# 1_2.net
KiCad netlist of a schematic drawn in Altium Designer
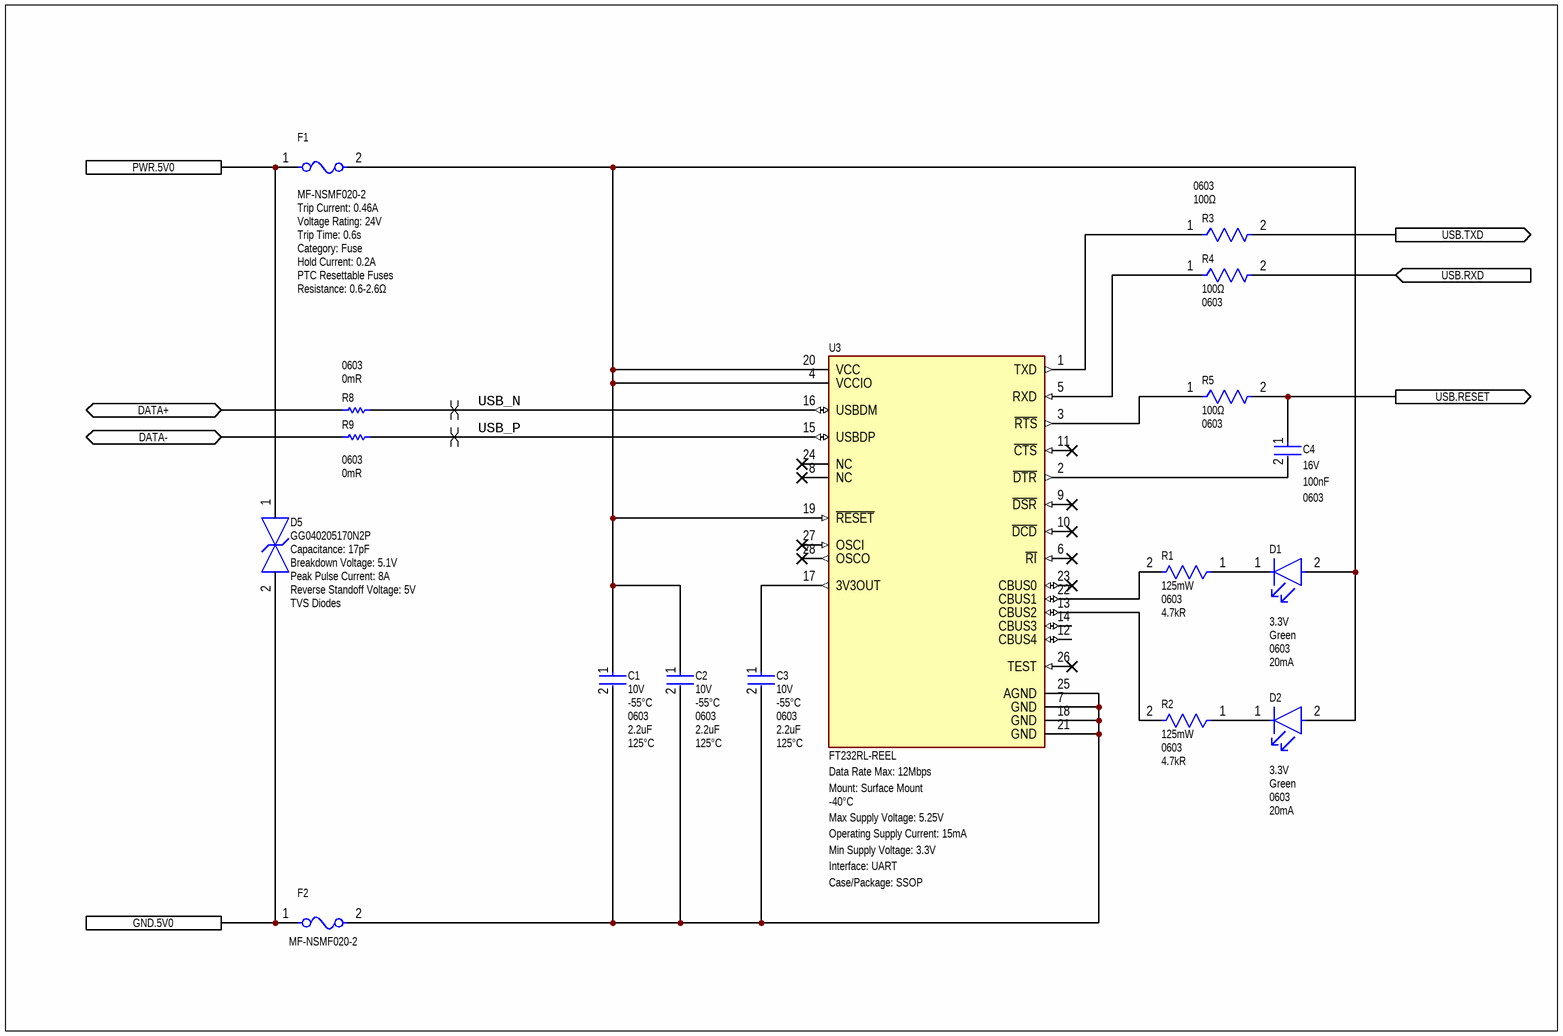
[diagram p0: Блок1.2.SchDoc]

(export (version "E")
  (design (tool "Eeschema 10.0.6"))
  (components
    (comp (ref "C1")
      (value "CL10B225KP8NFNC")
      (footprint "FP-CL10-IPC_A")
      (description "Cap Ceramic 2.2uF 10V X7R ±10% Pad SMD 0603 +125°C T/R")
      (fields
        (field (name "VOLTAGE RATING") "10V")
        (field (name "MIN OPERATING TEMPERATURE") "-55°C")
        (field (name "CASE CODE (IMPERIAL)") "0603")
        (field (name "CAPACITANCE") "2.2uF")
        (field (name "MAX OPERATING TEMPERATURE") "125°C")
        (field (name "TOLERANCE") "10%")
      )
      (libsource (lib "Altium Content Vault") (part "b4654b650e69147ec39a6b967a45e02"))
    )
    (comp (ref "C2")
      (value "CL10B225KP8NFNC")
      (footprint "FP-CL10-IPC_A")
      (description "Cap Ceramic 2.2uF 10V X7R ±10% Pad SMD 0603 +125°C T/R")
      (fields
        (field (name "VOLTAGE RATING") "10V")
        (field (name "MIN OPERATING TEMPERATURE") "-55°C")
        (field (name "CASE CODE (IMPERIAL)") "0603")
        (field (name "CAPACITANCE") "2.2uF")
        (field (name "MAX OPERATING TEMPERATURE") "125°C")
        (field (name "TOLERANCE") "10%")
      )
      (libsource (lib "Altium Content Vault") (part "b4654b650e69147ec39a6b967a45e02"))
    )
    (comp (ref "C3")
      (value "CL10B225KP8NFNC")
      (footprint "FP-CL10-IPC_A")
      (description "Cap Ceramic 2.2uF 10V X7R ±10% Pad SMD 0603 +125°C T/R")
      (fields
        (field (name "VOLTAGE RATING") "10V")
        (field (name "MIN OPERATING TEMPERATURE") "-55°C")
        (field (name "CASE CODE (IMPERIAL)") "0603")
        (field (name "CAPACITANCE") "2.2uF")
        (field (name "MAX OPERATING TEMPERATURE") "125°C")
        (field (name "TOLERANCE") "10%")
      )
      (libsource (lib "Altium Content Vault") (part "b4654b650e69147ec39a6b967a45e02"))
    )
    (comp (ref "C4")
      (value "CL10B104JO8NNND")
      (footprint "FP-CL10-IPC_B")
      (description "Cap Ceramic 100nF 16V X7R ±5% Pad SMD 0603 +125°C T/R")
      (fields
        (field (name "VOLTAGE RATING (DC)") "16V")
        (field (name "TOLERANCE") "5%")
        (field (name "CAPACITANCE") "100nF")
        (field (name "CASE/PACKAGE") "0603")
      )
      (libsource (lib "Altium Content Vault") (part "b4654b650e69147ec39a6b967a45e02"))
    )
    (comp (ref "D1")
      (value "APT1608ZGCK")
      (footprint "FP-APT1608ZGCK-MFG")
      (description "LED GREEN CLEAR CHIP SMD")
      (fields
        (field (name "FORWARD VOLTAGE") "3.3V")
        (field (name "COLOR") "Green")
        (field (name "CASE/PACKAGE") "0603")
        (field (name "FORWARD CURRENT") "20mA")
      )
      (libsource (lib "Altium Content Vault") (part "8706943c75ba83719d021d2fdc84c58"))
    )
    (comp (ref "D2")
      (value "APT1608ZGCK")
      (footprint "FP-APT1608ZGCK-MFG")
      (description "LED GREEN CLEAR CHIP SMD")
      (fields
        (field (name "FORWARD VOLTAGE") "3.3V")
        (field (name "COLOR") "Green")
        (field (name "CASE/PACKAGE") "0603")
        (field (name "FORWARD CURRENT") "20mA")
      )
      (libsource (lib "Altium Content Vault") (part "8706943c75ba83719d021d2fdc84c58"))
    )
    (comp (ref "D5")
      (value "GG040205170N2P")
      (footprint "FP-GG0402-IPC_A")
      (description "TVS DIODE 5V 10V 0402")
      (fields
        (field (name "OCTOPART") "https://octopart.com/gg040205170n2p-avx-81066082")
        (field (name "CAPACITANCE") "17pF")
        (field (name "MANUFACTURER") "AVX")
        (field (name "BREAKDOWN VOLTAGE") "5.1V")
        (field (name "PEAK PULSE CURRENT") "8A")
        (field (name "REVERSE STANDOFF VOLTAGE") "5V")
        (field (name "DEVICE CLASS L2") "TVS Diodes")
      )
      (libsource (lib "Altium Content Vault") (part "11bd9d59d340f0612179daf16ad9b72"))
    )
    (comp (ref "F1")
      (value "MF-NSMF020-2")
      (footprint "FP-MF-NSMF020-2-MFG")
      (description "PTC RESET FUSE 24V 200MA 1206")
      (fields
        (field (name "TRIP CURRENT") "0.46A")
        (field (name "VOLTAGE RATING") "24V")
        (field (name "TRIP TIME") "0.6s")
        (field (name "CATEGORY") "Fuse")
        (field (name "HOLD CURRENT") "0.2A")
        (field (name "DEVICE CLASS L2") "PTC Resettable Fuses")
        (field (name "MANUFACTURER") "Bourns")
        (field (name "OCTOPART") "https://octopart.com/mf-nsmf020-2-bourns-94649")
        (field (name "RESISTANCE") "0.6-2.6Ω")
      )
      (libsource (lib "Altium Content Vault") (part "5bcf9b9f640e542cf0359d10258e979"))
    )
    (comp (ref "F2")
      (value "MF-NSMF020-2")
      (footprint "FP-MF-NSMF020-2-MFG")
      (description "PTC RESET FUSE 24V 200MA 1206")
      (fields
        (field (name "MANUFACTURER") "Bourns")
        (field (name "OCTOPART") "https://octopart.com/mf-nsmf020-2-bourns-94649")
      )
      (libsource (lib "Altium Content Vault") (part "5bcf9b9f640e542cf0359d10258e979"))
    )
    (comp (ref "R1")
      (value "MCT06030C4701FP500")
      (footprint "FP-MCT0603-MFG")
      (description "RES SMD 100 OHM 1% 1/8W 0603")
      (fields
        (field (name "POWER RATING") "125mW")
        (field (name "CASE/PACKAGE") "0603")
        (field (name "RESISTANCE") "4.7kR")
        (field (name "TOLERANCE") "1%")
      )
      (libsource (lib "Altium Content Vault") (part "1029c3af85768c4190bb7ad29bc67b5"))
    )
    (comp (ref "R2")
      (value "MCT06030C4701FP500")
      (footprint "FP-MCT0603-MFG")
      (description "RES SMD 100 OHM 1% 1/8W 0603")
      (fields
        (field (name "POWER RATING") "125mW")
        (field (name "CASE/PACKAGE") "0603")
        (field (name "RESISTANCE") "4.7kR")
        (field (name "TOLERANCE") "1%")
      )
      (libsource (lib "Altium Content Vault") (part "1029c3af85768c4190bb7ad29bc67b5"))
    )
    (comp (ref "R3")
      (value "RT0603FRE07100RL")
      (footprint "FP-RT0603-IPC_A")
      (description "RES SMD 100 OHM 1% 1/10W 0603")
      (fields
        (field (name "MANUFACTURER") "Yageo")
        (field (name "RESISTANCE") "100Ω")
        (field (name "PACKAGE") "0603")
        (field (name "TOLERANCE") "0.01")
      )
      (libsource (lib "Altium Content Vault") (part "1029c3af85768c4190bb7ad29bc67b5"))
    )
    (comp (ref "R4")
      (value "RT0603FRE07100RL")
      (footprint "FP-RT0603-IPC_A")
      (description "RES SMD 100 OHM 1% 1/10W 0603")
      (fields
        (field (name "MANUFACTURER") "Yageo")
        (field (name "RESISTANCE") "100Ω")
        (field (name "PACKAGE") "0603")
        (field (name "TOLERANCE") "0.01")
      )
      (libsource (lib "Altium Content Vault") (part "1029c3af85768c4190bb7ad29bc67b5"))
    )
    (comp (ref "R5")
      (value "RT0603FRE07100RL")
      (footprint "FP-RT0603-IPC_A")
      (description "RES SMD 100 OHM 1% 1/10W 0603")
      (fields
        (field (name "MANUFACTURER") "Yageo")
        (field (name "RESISTANCE") "100Ω")
        (field (name "PACKAGE") "0603")
        (field (name "TOLERANCE") "0.01")
      )
      (libsource (lib "Altium Content Vault") (part "1029c3af85768c4190bb7ad29bc67b5"))
    )
    (comp (ref "R8")
      (value "CRCW06030000Z0EA")
      (footprint "RESC1609X50X30NL8T20")
      (description "Chip Resistor, 0 Ohm, Jumper, 100 mW, -55 to 155 degC, 0603 (1608 Metric), RoHS, Tape and Reel")
      (fields
        (field (name "MANUFACTURER") "Vishay")
        (field (name "PACKAGEREFERENCE") "0603")
        (field (name "MANUFACTURER PART NUMBER") "CRCW0603-0000Z0EA")
        (field (name "RESISTANCE") "0mR")
      )
      (libsource (lib "Altium Content Vault") (part "RES-2"))
    )
    (comp (ref "R9")
      (value "CRCW06030000Z0EA")
      (footprint "RESC1609X50X30NL8T20")
      (description "Chip Resistor, 0 Ohm, Jumper, 100 mW, -55 to 155 degC, 0603 (1608 Metric), RoHS, Tape and Reel")
      (fields
        (field (name "MANUFACTURER") "Vishay")
        (field (name "PACKAGEREFERENCE") "0603")
        (field (name "MANUFACTURER PART NUMBER") "CRCW0603-0000Z0EA")
        (field (name "RESISTANCE") "0mR")
      )
      (libsource (lib "Altium Content Vault") (part "RES-2"))
    )
    (comp (ref "U3")
      (value "FT232RL-REEL")
      (footprint "FP-SSOP-28-MFG")
      (description "IC USB FS SERIAL UART 28-SSOP")
      (fields
        (field (name "DATA RATE MAX") "12Mbps")
        (field (name "MOUNT") "Surface Mount")
        (field (name "MIN OPERATING TEMPERATURE") "-40°C")
        (field (name "MAX SUPPLY VOLTAGE") "5.25V")
        (field (name "OPERATING SUPPLY CURRENT") "15mA")
        (field (name "VOLTAGE") "5V")
        (field (name "MIN SUPPLY VOLTAGE") "3.3V")
        (field (name "INTERFACE") "UART")
        (field (name "CASE/PACKAGE") "SSOP")
      )
      (libsource (lib "Altium Content Vault") (part "fa727c664f4d88ca0f1b580aa0dd901"))
    )
  )
  (nets
    (net (code "1") (name "/DATA+") (class "Default")
      (node (ref "R8") (pin "1") (pinfunction "1_1") (pintype "passive"))
    )
    (net (code "2") (name "/DATA-") (class "Default")
      (node (ref "R9") (pin "1") (pinfunction "1_1") (pintype "passive"))
    )
    (net (code "3") (name "/GND.5V0") (class "Default")
      (node (ref "D5") (pin "2") (pinfunction "2_2") (pintype "passive"))
      (node (ref "F2") (pin "1") (pinfunction "1_1") (pintype "passive"))
    )
    (net (code "4") (name "/PWR.5V0") (class "Default")
      (node (ref "D5") (pin "1") (pinfunction "1_1") (pintype "passive"))
      (node (ref "F1") (pin "1") (pinfunction "1_1") (pintype "passive"))
    )
    (net (code "5") (name "/USB.RESET") (class "Default")
      (node (ref "C4") (pin "1") (pinfunction "1_1") (pintype "passive"))
      (node (ref "R5") (pin "2") (pinfunction "2_2") (pintype "passive"))
    )
    (net (code "6") (name "/USB.RXD") (class "Default")
      (node (ref "R4") (pin "2") (pinfunction "2_2") (pintype "passive"))
    )
    (net (code "7") (name "/USB.TXD") (class "Default")
      (node (ref "R3") (pin "2") (pinfunction "2_2") (pintype "passive"))
    )
    (net (code "8") (name "/USB_N") (class "Default")
      (node (ref "R8") (pin "2") (pinfunction "2_2") (pintype "passive"))
      (node (ref "U3") (pin "16") (pinfunction "USBDM_16") (pintype "bidirectional"))
    )
    (net (code "9") (name "/USB_P") (class "Default")
      (node (ref "R9") (pin "2") (pinfunction "2_2") (pintype "passive"))
      (node (ref "U3") (pin "15") (pinfunction "USBDP_15") (pintype "bidirectional"))
    )
    (net (code "10") (name "Net-(D1-A)") (class "Default")
      (node (ref "C1") (pin "1") (pinfunction "1_1") (pintype "passive"))
      (node (ref "C2") (pin "1") (pinfunction "1_1") (pintype "passive"))
      (node (ref "D1") (pin "2") (pinfunction "A_2") (pintype "passive"))
      (node (ref "D2") (pin "2") (pinfunction "A_2") (pintype "passive"))
      (node (ref "F1") (pin "2") (pinfunction "2_2") (pintype "passive"))
      (node (ref "U3") (pin "19") (pinfunction "~{RESET}_19") (pintype "input"))
      (node (ref "U3") (pin "20") (pinfunction "VCC_20") (pintype "power_in"))
      (node (ref "U3") (pin "4") (pinfunction "VCCIO_4") (pintype "power_in"))
    )
    (net (code "11") (name "Net-(D1-C)") (class "Default")
      (node (ref "D1") (pin "1") (pinfunction "C_1") (pintype "passive"))
      (node (ref "R1") (pin "1") (pinfunction "1_1") (pintype "passive"))
    )
    (net (code "12") (name "Net-(D2-C)") (class "Default")
      (node (ref "D2") (pin "1") (pinfunction "C_1") (pintype "passive"))
      (node (ref "R2") (pin "1") (pinfunction "1_1") (pintype "passive"))
    )
    (net (code "13") (name "Net-(U3-3V3OUT)") (class "Default")
      (node (ref "C3") (pin "1") (pinfunction "1_1") (pintype "passive"))
      (node (ref "U3") (pin "17") (pinfunction "3V3OUT_17") (pintype "output"))
    )
    (net (code "14") (name "Net-(U3-AGND)") (class "Default")
      (node (ref "C1") (pin "2") (pinfunction "2_2") (pintype "passive"))
      (node (ref "C2") (pin "2") (pinfunction "2_2") (pintype "passive"))
      (node (ref "C3") (pin "2") (pinfunction "2_2") (pintype "passive"))
      (node (ref "F2") (pin "2") (pinfunction "2_2") (pintype "passive"))
      (node (ref "U3") (pin "18") (pinfunction "GND_18") (pintype "power_in"))
      (node (ref "U3") (pin "21") (pinfunction "GND_21") (pintype "power_in"))
      (node (ref "U3") (pin "25") (pinfunction "AGND_25") (pintype "power_in"))
      (node (ref "U3") (pin "7") (pinfunction "GND_7") (pintype "power_in"))
    )
    (net (code "15") (name "Net-(U3-CBUS1)") (class "Default")
      (node (ref "R1") (pin "2") (pinfunction "2_2") (pintype "passive"))
      (node (ref "U3") (pin "22") (pinfunction "CBUS1_22") (pintype "bidirectional"))
    )
    (net (code "16") (name "Net-(U3-CBUS2)") (class "Default")
      (node (ref "R2") (pin "2") (pinfunction "2_2") (pintype "passive"))
      (node (ref "U3") (pin "13") (pinfunction "CBUS2_13") (pintype "bidirectional"))
    )
    (net (code "17") (name "Net-(U3-RXD)") (class "Default")
      (node (ref "R4") (pin "1") (pinfunction "1_1") (pintype "passive"))
      (node (ref "U3") (pin "5") (pinfunction "RXD_5") (pintype "input"))
    )
    (net (code "18") (name "Net-(U3-TXD)") (class "Default")
      (node (ref "R3") (pin "1") (pinfunction "1_1") (pintype "passive"))
      (node (ref "U3") (pin "1") (pinfunction "TXD_1") (pintype "output"))
    )
    (net (code "19") (name "Net-(U3-~{DTR})") (class "Default")
      (node (ref "C4") (pin "2") (pinfunction "2_2") (pintype "passive"))
      (node (ref "U3") (pin "2") (pinfunction "~{DTR}_2") (pintype "output"))
    )
    (net (code "20") (name "Net-(U3-~{RTS})") (class "Default")
      (node (ref "R5") (pin "1") (pinfunction "1_1") (pintype "passive"))
      (node (ref "U3") (pin "3") (pinfunction "~{RTS}_3") (pintype "output"))
    )
    (net (code "21") (name "unconnected-(U3-CBUS0-Pad23)") (class "Default")
      (node (ref "U3") (pin "23") (pinfunction "CBUS0_23") (pintype "bidirectional+no_connect"))
    )
    (net (code "22") (name "unconnected-(U3-CBUS3-Pad14)") (class "Default")
      (node (ref "U3") (pin "14") (pinfunction "CBUS3_14") (pintype "bidirectional"))
    )
    (net (code "23") (name "unconnected-(U3-CBUS4-Pad12)") (class "Default")
      (node (ref "U3") (pin "12") (pinfunction "CBUS4_12") (pintype "bidirectional"))
    )
    (net (code "24") (name "unconnected-(U3-NC-Pad8)") (class "Default")
      (node (ref "U3") (pin "8") (pinfunction "NC_8") (pintype "passive+no_connect"))
    )
    (net (code "25") (name "unconnected-(U3-NC-Pad24)") (class "Default")
      (node (ref "U3") (pin "24") (pinfunction "NC_24") (pintype "passive+no_connect"))
    )
    (net (code "26") (name "unconnected-(U3-OSCI-Pad27)") (class "Default")
      (node (ref "U3") (pin "27") (pinfunction "OSCI_27") (pintype "input+no_connect"))
    )
    (net (code "27") (name "unconnected-(U3-OSCO-Pad28)") (class "Default")
      (node (ref "U3") (pin "28") (pinfunction "OSCO_28") (pintype "output+no_connect"))
    )
    (net (code "28") (name "unconnected-(U3-TEST-Pad26)") (class "Default")
      (node (ref "U3") (pin "26") (pinfunction "TEST_26") (pintype "input+no_connect"))
    )
    (net (code "29") (name "unconnected-(U3-~{CTS}-Pad11)") (class "Default")
      (node (ref "U3") (pin "11") (pinfunction "~{CTS}_11") (pintype "input+no_connect"))
    )
    (net (code "30") (name "unconnected-(U3-~{DCD}-Pad10)") (class "Default")
      (node (ref "U3") (pin "10") (pinfunction "~{DCD}_10") (pintype "input+no_connect"))
    )
    (net (code "31") (name "unconnected-(U3-~{DSR}-Pad9)") (class "Default")
      (node (ref "U3") (pin "9") (pinfunction "~{DSR}_9") (pintype "input+no_connect"))
    )
    (net (code "32") (name "unconnected-(U3-~{RI}-Pad6)") (class "Default")
      (node (ref "U3") (pin "6") (pinfunction "~{RI}_6") (pintype "input+no_connect"))
    )
  )
)
